# 1_0mm_0_5mm_FPC_stick.net
KiCad netlist of a schematic drawn in EAGLE
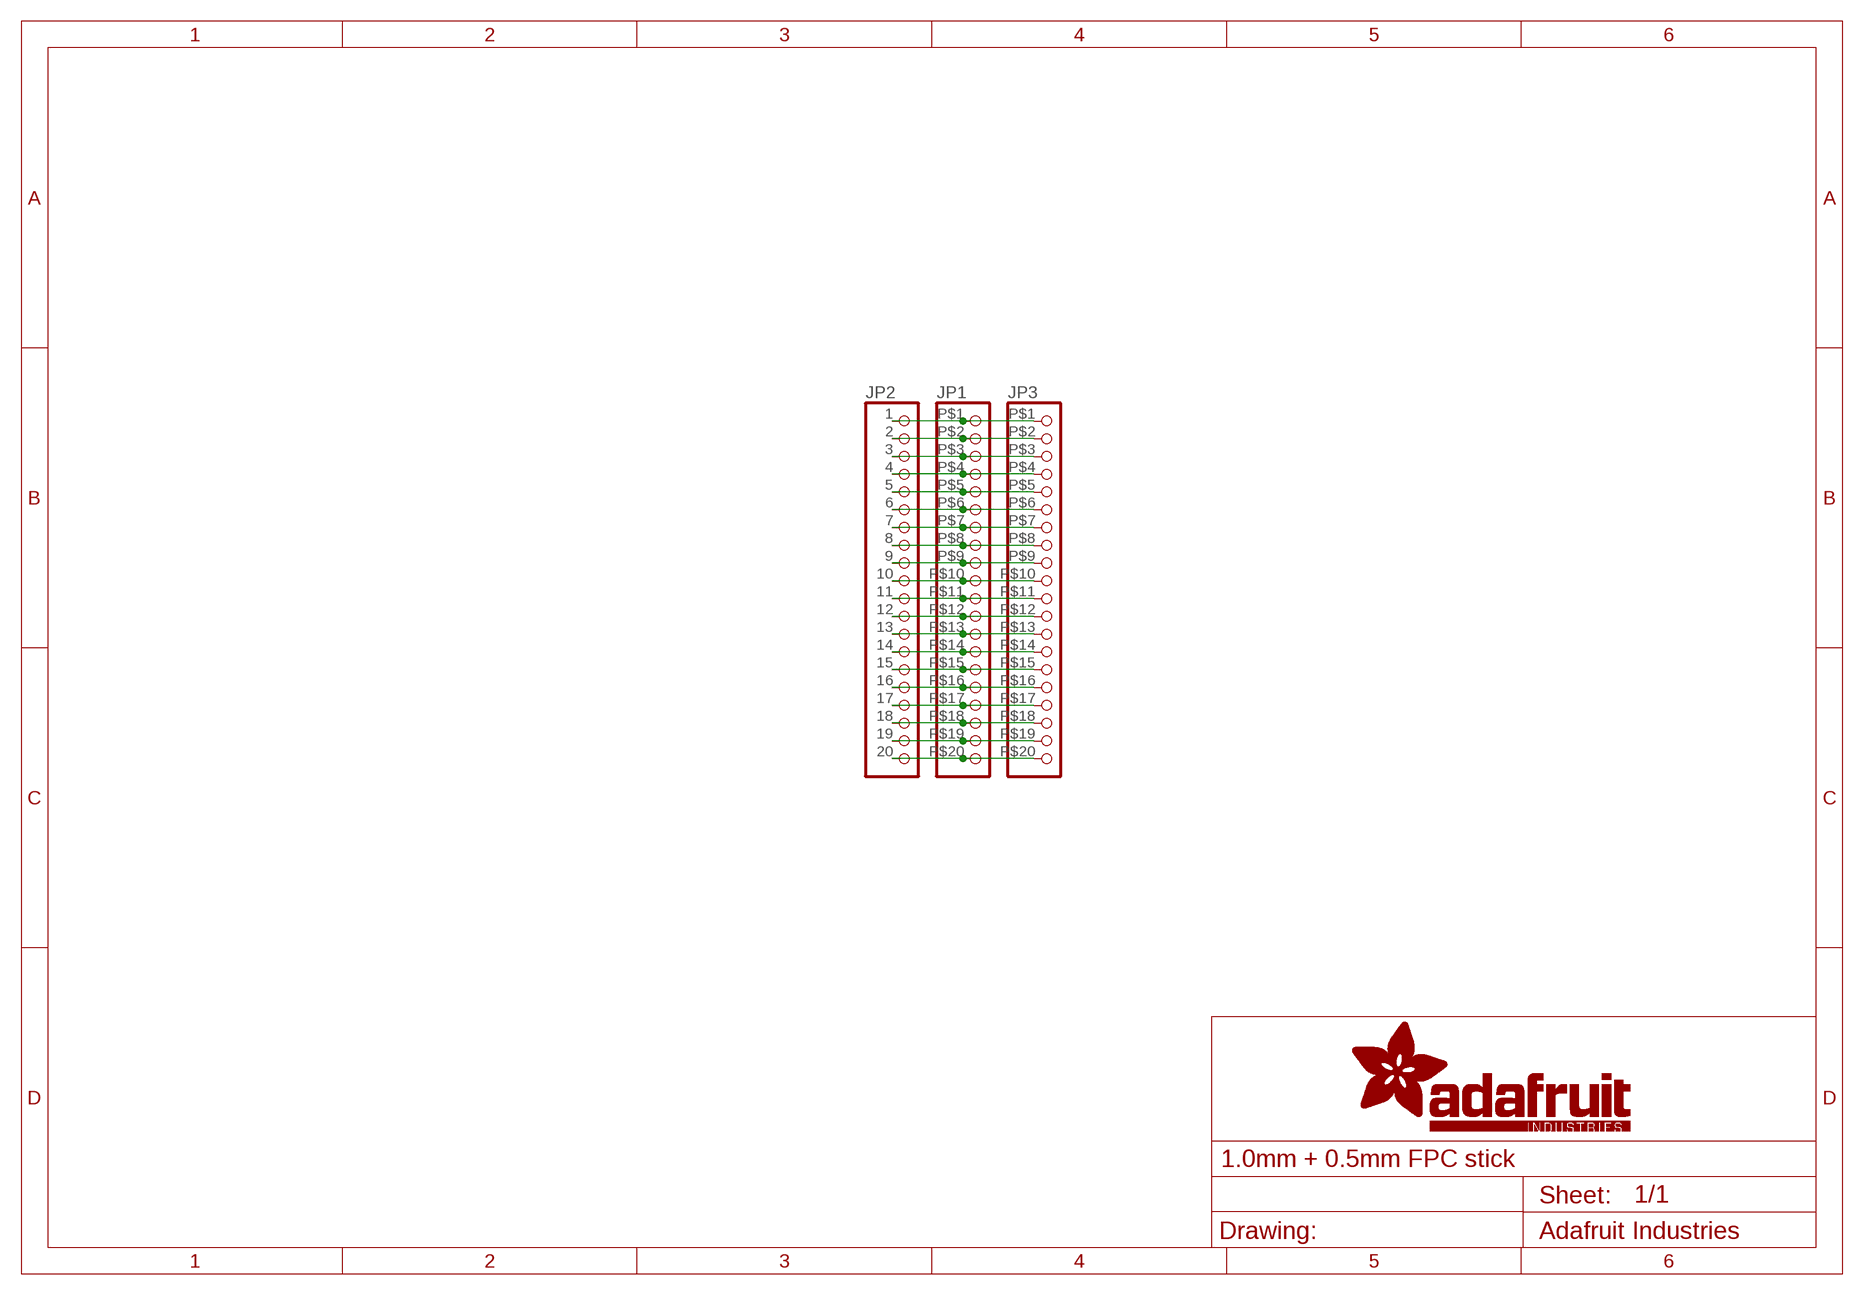
[diagram p0: schematic, sheet 1]

(export (version "E")
  (design (tool "Eeschema 10.0.6"))
  (components
    (comp (ref "JP1")
      (value "HEADER-1X20FPC_1.0MM")
      (footprint "eagle-import:FPC_GENERIC_1.0MM_20PIN")
      (libsource (lib "eagle-import") (part "HEADER-1X20FPC_1.0MM"))
    )
    (comp (ref "JP2")
      (value "HEADER-1X20ROUND")
      (footprint "eagle-import:1X20_ROUND")
      (libsource (lib "eagle-import") (part "HEADER-1X20ROUND"))
    )
    (comp (ref "JP3")
      (value "HEADER-1X20FPC_0.5MM")
      (footprint "eagle-import:FPC_GENERIC_0.5MM_20PIN")
      (libsource (lib "eagle-import") (part "HEADER-1X20FPC_0.5MM"))
    )
  )
  (nets
    (net (code "1") (name "Net-(JP1-1)") (class "Default")
      (node (ref "JP1") (pin "P$1") (pinfunction "1_P$1") (pintype "passive"))
      (node (ref "JP2") (pin "1") (pinfunction "1_1") (pintype "passive"))
      (node (ref "JP3") (pin "P$1") (pinfunction "1_P$1") (pintype "passive"))
    )
    (net (code "2") (name "Net-(JP1-2)") (class "Default")
      (node (ref "JP1") (pin "P$2") (pinfunction "2_P$2") (pintype "passive"))
      (node (ref "JP2") (pin "2") (pinfunction "2_2") (pintype "passive"))
      (node (ref "JP3") (pin "P$2") (pinfunction "2_P$2") (pintype "passive"))
    )
    (net (code "3") (name "Net-(JP1-3)") (class "Default")
      (node (ref "JP1") (pin "P$3") (pinfunction "3_P$3") (pintype "passive"))
      (node (ref "JP2") (pin "3") (pinfunction "3_3") (pintype "passive"))
      (node (ref "JP3") (pin "P$3") (pinfunction "3_P$3") (pintype "passive"))
    )
    (net (code "4") (name "Net-(JP1-4)") (class "Default")
      (node (ref "JP1") (pin "P$4") (pinfunction "4_P$4") (pintype "passive"))
      (node (ref "JP2") (pin "4") (pinfunction "4_4") (pintype "passive"))
      (node (ref "JP3") (pin "P$4") (pinfunction "4_P$4") (pintype "passive"))
    )
    (net (code "5") (name "Net-(JP1-5)") (class "Default")
      (node (ref "JP1") (pin "P$5") (pinfunction "5_P$5") (pintype "passive"))
      (node (ref "JP2") (pin "5") (pinfunction "5_5") (pintype "passive"))
      (node (ref "JP3") (pin "P$5") (pinfunction "5_P$5") (pintype "passive"))
    )
    (net (code "6") (name "Net-(JP1-6)") (class "Default")
      (node (ref "JP1") (pin "P$6") (pinfunction "6_P$6") (pintype "passive"))
      (node (ref "JP2") (pin "6") (pinfunction "6_6") (pintype "passive"))
      (node (ref "JP3") (pin "P$6") (pinfunction "6_P$6") (pintype "passive"))
    )
    (net (code "7") (name "Net-(JP1-7)") (class "Default")
      (node (ref "JP1") (pin "P$7") (pinfunction "7_P$7") (pintype "passive"))
      (node (ref "JP2") (pin "7") (pinfunction "7_7") (pintype "passive"))
      (node (ref "JP3") (pin "P$7") (pinfunction "7_P$7") (pintype "passive"))
    )
    (net (code "8") (name "Net-(JP1-8)") (class "Default")
      (node (ref "JP1") (pin "P$8") (pinfunction "8_P$8") (pintype "passive"))
      (node (ref "JP2") (pin "8") (pinfunction "8_8") (pintype "passive"))
      (node (ref "JP3") (pin "P$8") (pinfunction "8_P$8") (pintype "passive"))
    )
    (net (code "9") (name "Net-(JP1-9)") (class "Default")
      (node (ref "JP1") (pin "P$9") (pinfunction "9_P$9") (pintype "passive"))
      (node (ref "JP2") (pin "9") (pinfunction "9_9") (pintype "passive"))
      (node (ref "JP3") (pin "P$9") (pinfunction "9_P$9") (pintype "passive"))
    )
    (net (code "10") (name "Net-(JP1-10)") (class "Default")
      (node (ref "JP1") (pin "P$10") (pinfunction "10_P$10") (pintype "passive"))
      (node (ref "JP2") (pin "10") (pinfunction "10_10") (pintype "passive"))
      (node (ref "JP3") (pin "P$10") (pinfunction "10_P$10") (pintype "passive"))
    )
    (net (code "11") (name "Net-(JP1-11)") (class "Default")
      (node (ref "JP1") (pin "P$11") (pinfunction "11_P$11") (pintype "passive"))
      (node (ref "JP2") (pin "11") (pinfunction "11_11") (pintype "passive"))
      (node (ref "JP3") (pin "P$11") (pinfunction "11_P$11") (pintype "passive"))
    )
    (net (code "12") (name "Net-(JP1-12)") (class "Default")
      (node (ref "JP1") (pin "P$12") (pinfunction "12_P$12") (pintype "passive"))
      (node (ref "JP2") (pin "12") (pinfunction "12_12") (pintype "passive"))
      (node (ref "JP3") (pin "P$12") (pinfunction "12_P$12") (pintype "passive"))
    )
    (net (code "13") (name "Net-(JP1-13)") (class "Default")
      (node (ref "JP1") (pin "P$13") (pinfunction "13_P$13") (pintype "passive"))
      (node (ref "JP2") (pin "13") (pinfunction "13_13") (pintype "passive"))
      (node (ref "JP3") (pin "P$13") (pinfunction "13_P$13") (pintype "passive"))
    )
    (net (code "14") (name "Net-(JP1-14)") (class "Default")
      (node (ref "JP1") (pin "P$14") (pinfunction "14_P$14") (pintype "passive"))
      (node (ref "JP2") (pin "14") (pinfunction "14_14") (pintype "passive"))
      (node (ref "JP3") (pin "P$14") (pinfunction "14_P$14") (pintype "passive"))
    )
    (net (code "15") (name "Net-(JP1-15)") (class "Default")
      (node (ref "JP1") (pin "P$15") (pinfunction "15_P$15") (pintype "passive"))
      (node (ref "JP2") (pin "15") (pinfunction "15_15") (pintype "passive"))
      (node (ref "JP3") (pin "P$15") (pinfunction "15_P$15") (pintype "passive"))
    )
    (net (code "16") (name "Net-(JP1-16)") (class "Default")
      (node (ref "JP1") (pin "P$16") (pinfunction "16_P$16") (pintype "passive"))
      (node (ref "JP2") (pin "16") (pinfunction "16_16") (pintype "passive"))
      (node (ref "JP3") (pin "P$16") (pinfunction "16_P$16") (pintype "passive"))
    )
    (net (code "17") (name "Net-(JP1-17)") (class "Default")
      (node (ref "JP1") (pin "P$17") (pinfunction "17_P$17") (pintype "passive"))
      (node (ref "JP2") (pin "17") (pinfunction "17_17") (pintype "passive"))
      (node (ref "JP3") (pin "P$17") (pinfunction "17_P$17") (pintype "passive"))
    )
    (net (code "18") (name "Net-(JP1-18)") (class "Default")
      (node (ref "JP1") (pin "P$18") (pinfunction "18_P$18") (pintype "passive"))
      (node (ref "JP2") (pin "18") (pinfunction "18_18") (pintype "passive"))
      (node (ref "JP3") (pin "P$18") (pinfunction "18_P$18") (pintype "passive"))
    )
    (net (code "19") (name "Net-(JP1-19)") (class "Default")
      (node (ref "JP1") (pin "P$19") (pinfunction "19_P$19") (pintype "passive"))
      (node (ref "JP2") (pin "19") (pinfunction "19_19") (pintype "passive"))
      (node (ref "JP3") (pin "P$19") (pinfunction "19_P$19") (pintype "passive"))
    )
    (net (code "20") (name "Net-(JP1-20)") (class "Default")
      (node (ref "JP1") (pin "P$20") (pinfunction "20_P$20") (pintype "passive"))
      (node (ref "JP2") (pin "20") (pinfunction "20_20") (pintype "passive"))
      (node (ref "JP3") (pin "P$20") (pinfunction "20_P$20") (pintype "passive"))
    )
  )
)
